# alimentaci_n.net
KiCad netlist of a schematic drawn in Altium Designer
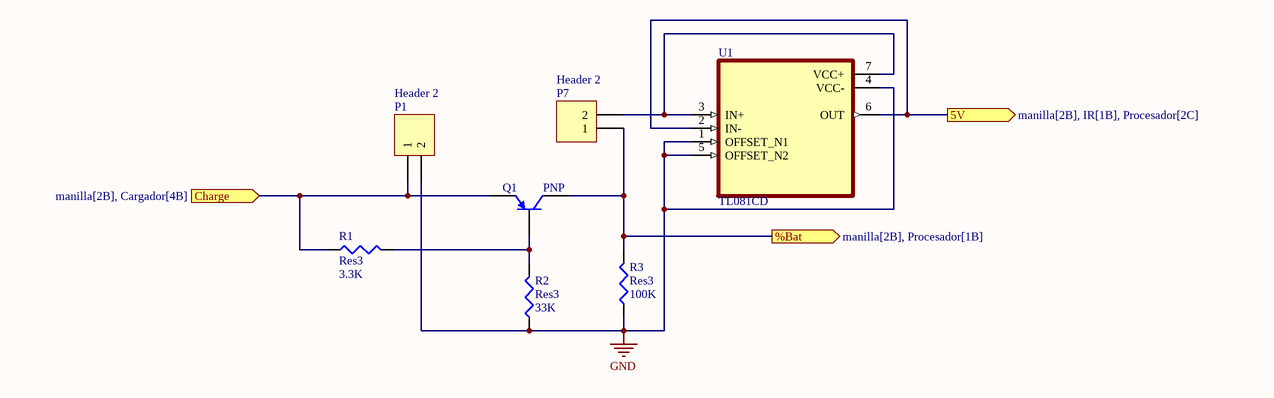
[diagram p0: alimentación.SchDoc]

(export (version "E")
  (design (tool "Eeschema 10.0.6"))
  (components
    (comp (ref "P1")
      (value "Header 2")
      (footprint "HDR1X2")
      (description "Header, 2-Pin")
      (fields (field (name "PUBLISHER") "Altium Limited"))
      (libsource (lib "") (part "Header 2_1"))
    )
    (comp (ref "P7")
      (value "Header 2")
      (footprint "HDR1X2")
      (description "Header, 2-Pin")
      (fields (field (name "PUBLISHER") "Altium Limited"))
      (libsource (lib "Miscellaneous Connectors") (part "Header 2"))
    )
    (comp (ref "Q1")
      (value "PNP")
      (footprint "SOT-23B_M")
      (description "PNP Bipolar Transistor")
      (fields (field (name "PUBLISHER") "Altium Limited"))
      (libsource (lib "Miscellaneous Devices") (part "PNP"))
    )
    (comp (ref "R1")
      (value "Res3")
      (footprint "J1-0603")
      (description "Resistor")
      (fields (field (name "ALTIUM_VALUE") "3.3K") (field (name "PUBLISHER") "Altium Limited"))
      (libsource (lib "Miscellaneous Devices") (part "Res3"))
    )
    (comp (ref "R2")
      (value "Res3")
      (footprint "J1-0603")
      (description "Resistor")
      (fields (field (name "ALTIUM_VALUE") "33K") (field (name "PUBLISHER") "Altium Limited"))
      (libsource (lib "Miscellaneous Devices") (part "Res3"))
    )
    (comp (ref "R3")
      (value "Res3")
      (footprint "J1-0603")
      (description "Resistor")
      (fields (field (name "ALTIUM_VALUE") "100K") (field (name "PUBLISHER") "Altium Limited"))
      (libsource (lib "Miscellaneous Devices") (part "Res3"))
    )
    (comp (ref "U1")
      (value "TL081CD")
      (footprint "SOIC127P599X175-8N")
      (description "High Slew Rate JFET-Input Operational Amplifier 8-SOIC 0 to 70")
      (fields (field (name "MF") "Texas Instruments"))
      (libsource (lib "TL081CD") (part "TL081CD"))
    )
  )
  (nets
    (net (code "1") (name "/%Bat") (class "Default")
      (node (ref "P7") (pin "1") (pinfunction "1_1") (pintype "passive"))
      (node (ref "Q1") (pin "1") (pinfunction "C_1") (pintype "passive"))
      (node (ref "R3") (pin "2") (pinfunction "2_2") (pintype "passive"))
    )
    (net (code "2") (name "/5V") (class "Default")
      (node (ref "U1") (pin "2") (pinfunction "IN-_2") (pintype "input"))
      (node (ref "U1") (pin "6") (pinfunction "OUT_6") (pintype "output"))
    )
    (net (code "3") (name "/Charge") (class "Default")
      (node (ref "P1") (pin "1") (pinfunction "1_1") (pintype "passive"))
      (node (ref "Q1") (pin "3") (pinfunction "E_3") (pintype "passive"))
      (node (ref "R1") (pin "1") (pinfunction "1_1") (pintype "passive"))
    )
    (net (code "4") (name "GND") (class "Default")
      (node (ref "P1") (pin "2") (pinfunction "2_2") (pintype "passive"))
      (node (ref "R2") (pin "1") (pinfunction "1_1") (pintype "passive"))
      (node (ref "R3") (pin "1") (pinfunction "1_1") (pintype "passive"))
      (node (ref "U1") (pin "1") (pinfunction "OFFSET_N1_1") (pintype "input"))
      (node (ref "U1") (pin "4") (pinfunction "VCC-_4") (pintype "power_in"))
      (node (ref "U1") (pin "5") (pinfunction "OFFSET_N2_5") (pintype "input"))
    )
    (net (code "5") (name "Net-(Q1-B)") (class "Default")
      (node (ref "Q1") (pin "2") (pinfunction "B_2") (pintype "passive"))
      (node (ref "R1") (pin "2") (pinfunction "2_2") (pintype "passive"))
      (node (ref "R2") (pin "2") (pinfunction "2_2") (pintype "passive"))
    )
    (net (code "6") (name "Net-(U1-IN+)") (class "Default")
      (node (ref "P7") (pin "2") (pinfunction "2_2") (pintype "passive"))
      (node (ref "U1") (pin "3") (pinfunction "IN+_3") (pintype "input"))
      (node (ref "U1") (pin "7") (pinfunction "VCC+_7") (pintype "power_in"))
    )
  )
)
